# STM32L4xx-v1_1_0.net
KiCad netlist of a schematic drawn in EAGLE
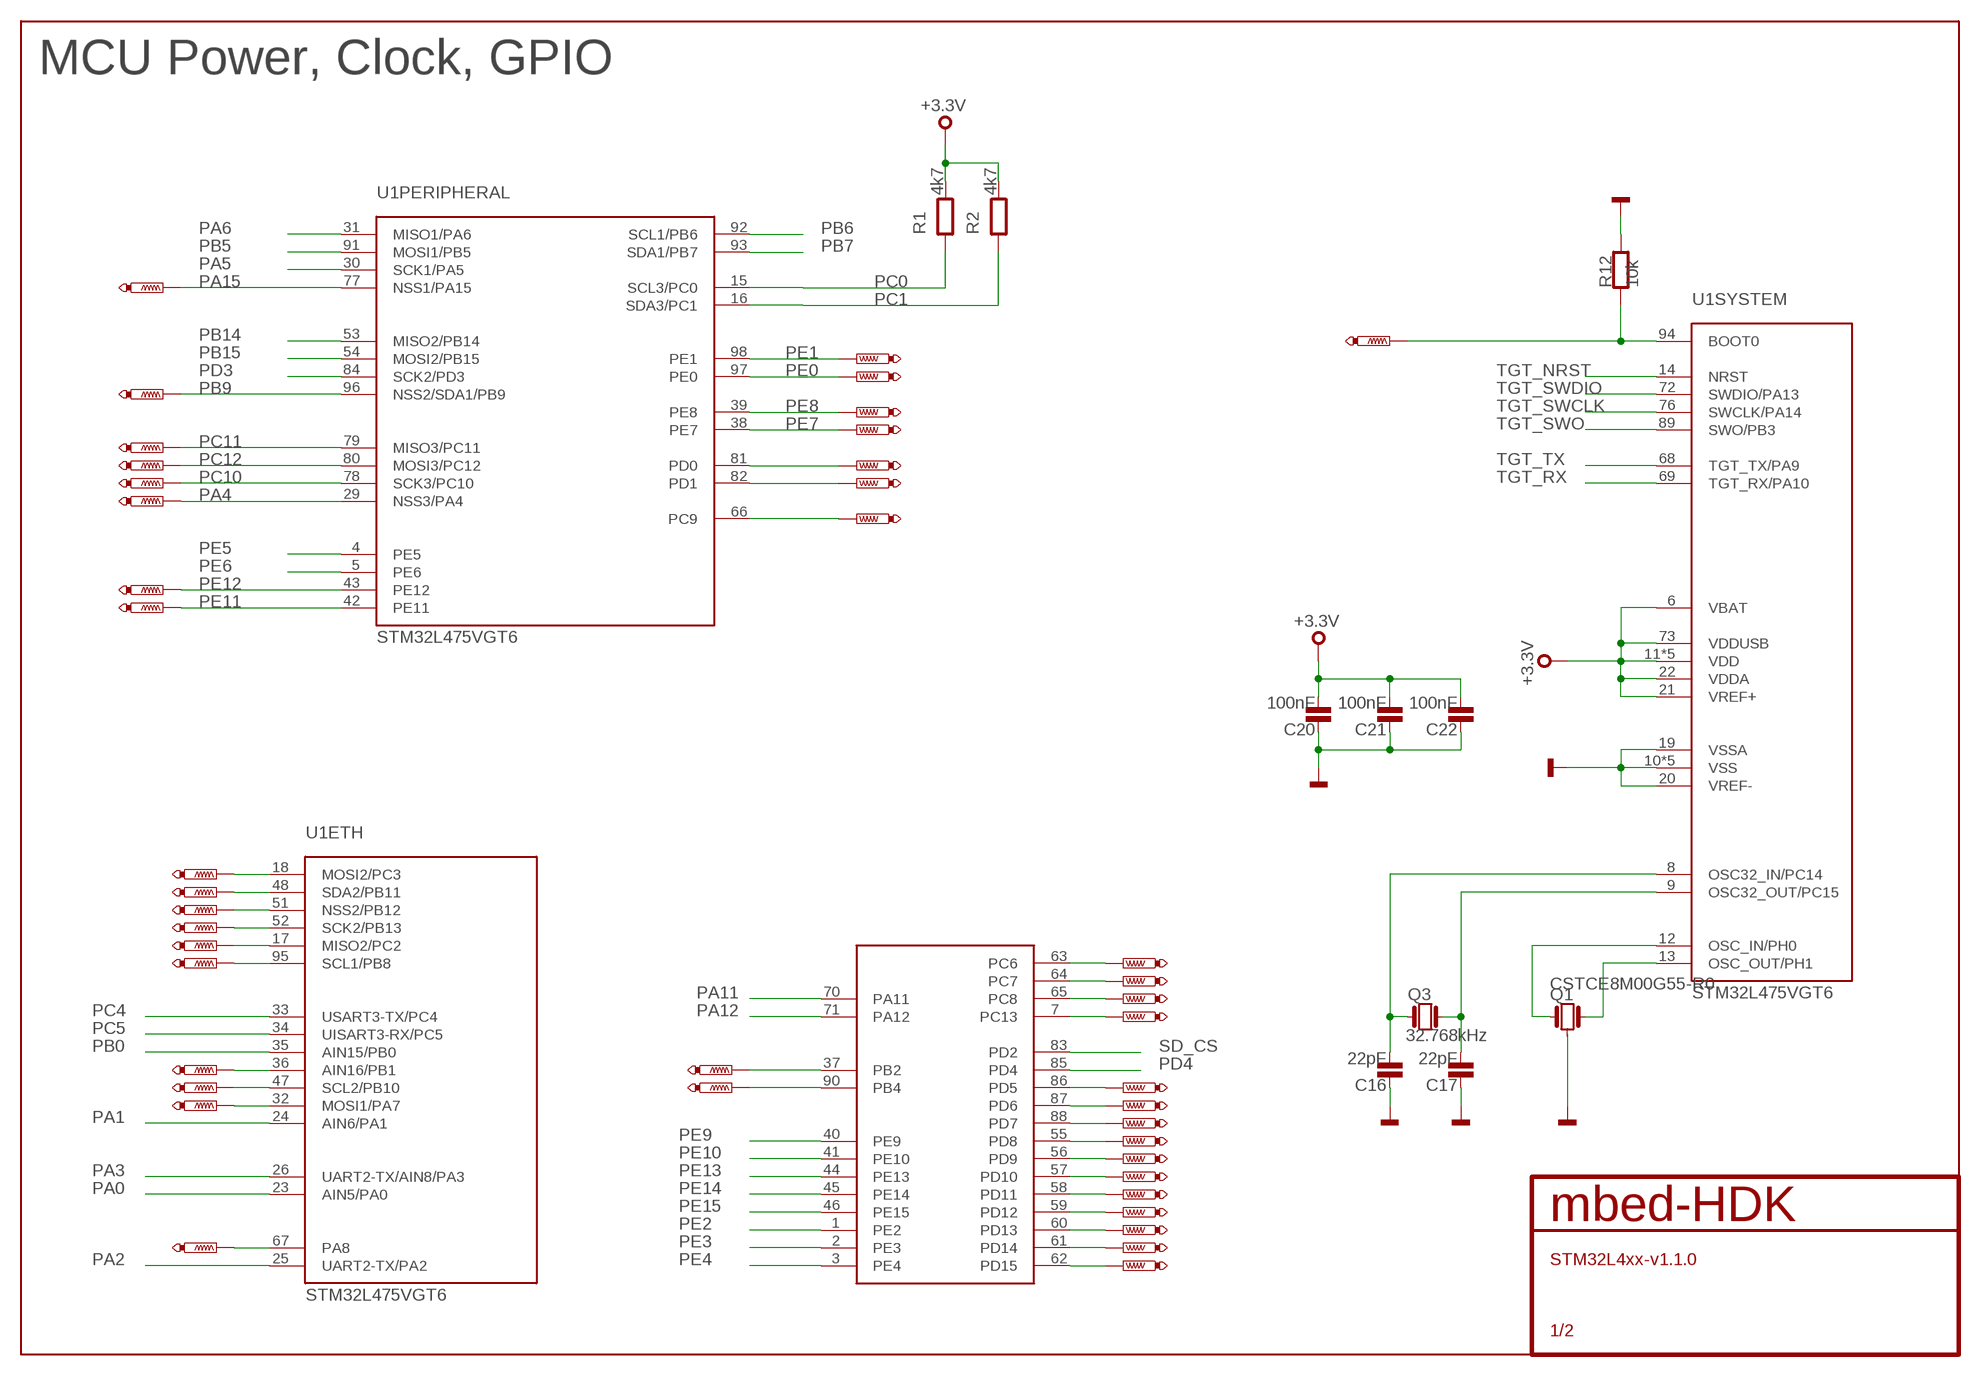
[diagram p0: schematic, sheet 1]
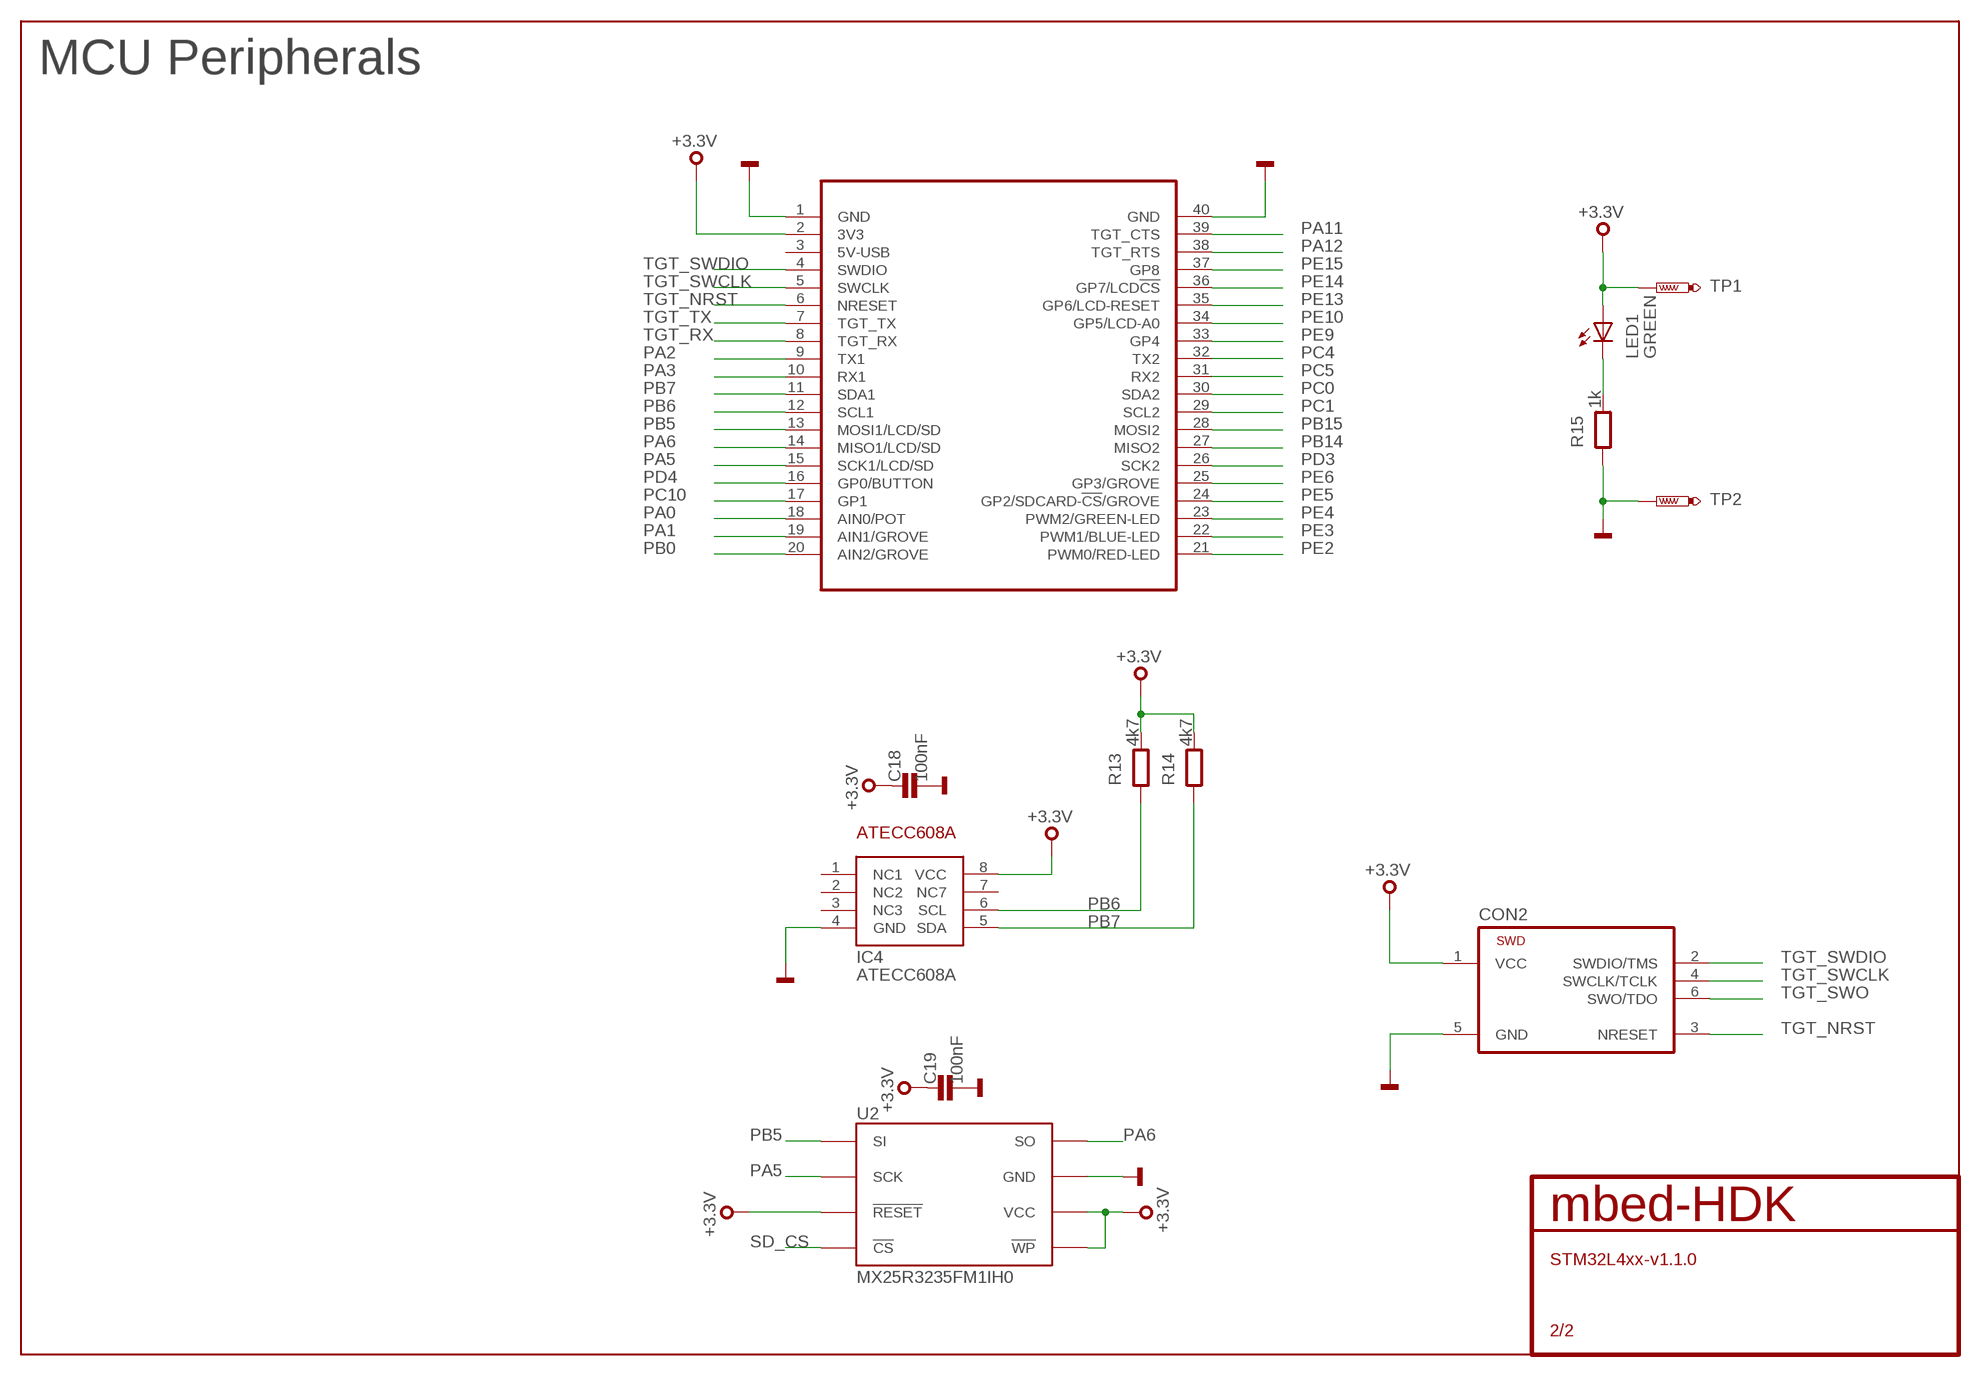
[diagram p1: schematic, sheet 2]

(export (version "E")
  (design (tool "Eeschema 10.0.6"))
  (components
    (comp (ref "C18")
      (value "100nF")
      (footprint "eagle-import:0402")
      (libsource (lib "eagle-import") (part "C0402"))
    )
    (comp (ref "C19")
      (value "100nF")
      (footprint "eagle-import:0402")
      (libsource (lib "eagle-import") (part "C0402"))
    )
    (comp (ref "CON2")
      (value "TC2030-CTX-NL")
      (footprint "eagle-import:TC2030-CTX-NL")
      (libsource (lib "eagle-import") (part "TC2030-CTX-NL"))
    )
    (comp (ref "IC4")
      (value "ATECC608A")
      (footprint "eagle-import:SO8")
      (libsource (lib "eagle-import") (part "ATECC608A"))
    )
    (comp (ref "LED1")
      (value "GREEN")
      (footprint "eagle-import:CHIPLED_0603")
      (fields (field (name "MF") "Wurth Electronics Inc"))
      (libsource (lib "eagle-import") (part "SMD_LED0603"))
    )
    (comp (ref "MOD1")
      (value "MODULE_DAUGHTER")
      (footprint "eagle-import:MODULE_DAUGHTER")
      (libsource (lib "eagle-import") (part "MODULE_DAUGHTER"))
    )
    (comp (ref "R13")
      (value "4k7")
      (footprint "eagle-import:0402")
      (libsource (lib "eagle-import") (part "R0402"))
    )
    (comp (ref "R14")
      (value "4k7")
      (footprint "eagle-import:0402")
      (libsource (lib "eagle-import") (part "R0402"))
    )
    (comp (ref "R15")
      (value "1k")
      (footprint "eagle-import:0603")
      (libsource (lib "eagle-import") (part "R0603"))
    )
    (comp (ref "TP1")
      (value "TEST-POINT-50R-PTH")
      (footprint "eagle-import:TP50-PTH")
      (libsource (lib "eagle-import") (part "TEST-POINT-50R-PTH"))
    )
    (comp (ref "TP2")
      (value "TEST-POINT-50R-PTH")
      (footprint "eagle-import:TP50-PTH")
      (libsource (lib "eagle-import") (part "TEST-POINT-50R-PTH"))
    )
    (comp (ref "U2")
      (value "MX25R3235FM1IH0")
      (footprint "eagle-import:SO8")
      (fields (field (name "MF") "Macronix"))
      (libsource (lib "eagle-import") (part "MX25R3235FM1IH0"))
    )
    (comp (ref "C16")
      (value "22pF")
      (footprint "eagle-import:0603")
      (libsource (lib "eagle-import") (part "C0603"))
    )
    (comp (ref "C17")
      (value "22pF")
      (footprint "eagle-import:0603")
      (libsource (lib "eagle-import") (part "C0603"))
    )
    (comp (ref "C20")
      (value "100nF")
      (footprint "eagle-import:0402")
      (libsource (lib "eagle-import") (part "C0402"))
    )
    (comp (ref "C21")
      (value "100nF")
      (footprint "eagle-import:0402")
      (libsource (lib "eagle-import") (part "C0402"))
    )
    (comp (ref "C22")
      (value "100nF")
      (footprint "eagle-import:0402")
      (libsource (lib "eagle-import") (part "C0402"))
    )
    (comp (ref "Q1")
      (value "CSTCE8M00G55-R0")
      (footprint "eagle-import:CSTCE8M00G55-R0")
      (fields (field (name "MF") "Murata"))
      (libsource (lib "eagle-import") (part "CSTCE8M00G55-R0"))
    )
    (comp (ref "Q3")
      (value "32.768kHz")
      (footprint "eagle-import:FC135")
      (libsource (lib "eagle-import") (part "GENERIC-CRYSTAL_FC135"))
    )
    (comp (ref "R1")
      (value "4k7")
      (footprint "eagle-import:0402")
      (libsource (lib "eagle-import") (part "R0402"))
    )
    (comp (ref "R2")
      (value "4k7")
      (footprint "eagle-import:0402")
      (libsource (lib "eagle-import") (part "R0402"))
    )
    (comp (ref "R12")
      (value "10k")
      (footprint "eagle-import:0402")
      (libsource (lib "eagle-import") (part "R0402"))
    )
    (comp (ref "TP3")
      (value "PTR1TP06R")
      (footprint "eagle-import:TP06R")
      (libsource (lib "eagle-import") (part "PTR1TP06R"))
    )
    (comp (ref "TP4")
      (value "PTR1TP06R")
      (footprint "eagle-import:TP06R")
      (libsource (lib "eagle-import") (part "PTR1TP06R"))
    )
    (comp (ref "TP5")
      (value "PTR1TP06R")
      (footprint "eagle-import:TP06R")
      (libsource (lib "eagle-import") (part "PTR1TP06R"))
    )
    (comp (ref "TP6")
      (value "PTR1TP06R")
      (footprint "eagle-import:TP06R")
      (libsource (lib "eagle-import") (part "PTR1TP06R"))
    )
    (comp (ref "TP7")
      (value "PTR1TP06R")
      (footprint "eagle-import:TP06R")
      (libsource (lib "eagle-import") (part "PTR1TP06R"))
    )
    (comp (ref "TP8")
      (value "PTR1TP06R")
      (footprint "eagle-import:TP06R")
      (libsource (lib "eagle-import") (part "PTR1TP06R"))
    )
    (comp (ref "TP9")
      (value "PTR1TP06R")
      (footprint "eagle-import:TP06R")
      (libsource (lib "eagle-import") (part "PTR1TP06R"))
    )
    (comp (ref "TP10")
      (value "PTR1TP06R")
      (footprint "eagle-import:TP06R")
      (libsource (lib "eagle-import") (part "PTR1TP06R"))
    )
    (comp (ref "TP11")
      (value "PTR1TP06R")
      (footprint "eagle-import:TP06R")
      (libsource (lib "eagle-import") (part "PTR1TP06R"))
    )
    (comp (ref "TP12")
      (value "PTR1TP06R")
      (footprint "eagle-import:TP06R")
      (libsource (lib "eagle-import") (part "PTR1TP06R"))
    )
    (comp (ref "TP13")
      (value "PTR1TP06R")
      (footprint "eagle-import:TP06R")
      (libsource (lib "eagle-import") (part "PTR1TP06R"))
    )
    (comp (ref "TP14")
      (value "PTR1TP06R")
      (footprint "eagle-import:TP06R")
      (libsource (lib "eagle-import") (part "PTR1TP06R"))
    )
    (comp (ref "TP15")
      (value "PTR1TP06R")
      (footprint "eagle-import:TP06R")
      (libsource (lib "eagle-import") (part "PTR1TP06R"))
    )
    (comp (ref "TP16")
      (value "PTR1TP06R")
      (footprint "eagle-import:TP06R")
      (libsource (lib "eagle-import") (part "PTR1TP06R"))
    )
    (comp (ref "TP17")
      (value "PTR1TP06R")
      (footprint "eagle-import:TP06R")
      (libsource (lib "eagle-import") (part "PTR1TP06R"))
    )
    (comp (ref "TP18")
      (value "PTR1TP06R")
      (footprint "eagle-import:TP06R")
      (libsource (lib "eagle-import") (part "PTR1TP06R"))
    )
    (comp (ref "TP19")
      (value "PTR1TP06R")
      (footprint "eagle-import:TP06R")
      (libsource (lib "eagle-import") (part "PTR1TP06R"))
    )
    (comp (ref "TP20")
      (value "PTR1TP06R")
      (footprint "eagle-import:TP06R")
      (libsource (lib "eagle-import") (part "PTR1TP06R"))
    )
    (comp (ref "TP21")
      (value "PTR1TP06R")
      (footprint "eagle-import:TP06R")
      (libsource (lib "eagle-import") (part "PTR1TP06R"))
    )
    (comp (ref "TP22")
      (value "PTR1TP06R")
      (footprint "eagle-import:TP06R")
      (libsource (lib "eagle-import") (part "PTR1TP06R"))
    )
    (comp (ref "TP23")
      (value "PTR1TP06R")
      (footprint "eagle-import:TP06R")
      (libsource (lib "eagle-import") (part "PTR1TP06R"))
    )
    (comp (ref "TP24")
      (value "PTR1TP06R")
      (footprint "eagle-import:TP06R")
      (libsource (lib "eagle-import") (part "PTR1TP06R"))
    )
    (comp (ref "TP25")
      (value "PTR1TP06R")
      (footprint "eagle-import:TP06R")
      (libsource (lib "eagle-import") (part "PTR1TP06R"))
    )
    (comp (ref "TP26")
      (value "PTR1TP06R")
      (footprint "eagle-import:TP06R")
      (libsource (lib "eagle-import") (part "PTR1TP06R"))
    )
    (comp (ref "TP27")
      (value "PTR1TP06R")
      (footprint "eagle-import:TP06R")
      (libsource (lib "eagle-import") (part "PTR1TP06R"))
    )
    (comp (ref "TP28")
      (value "PTR1TP06R")
      (footprint "eagle-import:TP06R")
      (libsource (lib "eagle-import") (part "PTR1TP06R"))
    )
    (comp (ref "TP29")
      (value "PTR1TP06R")
      (footprint "eagle-import:TP06R")
      (libsource (lib "eagle-import") (part "PTR1TP06R"))
    )
    (comp (ref "TP30")
      (value "PTR1TP06R")
      (footprint "eagle-import:TP06R")
      (libsource (lib "eagle-import") (part "PTR1TP06R"))
    )
    (comp (ref "TP31")
      (value "PTR1TP06R")
      (footprint "eagle-import:TP06R")
      (libsource (lib "eagle-import") (part "PTR1TP06R"))
    )
    (comp (ref "TP32")
      (value "PTR1TP06R")
      (footprint "eagle-import:TP06R")
      (libsource (lib "eagle-import") (part "PTR1TP06R"))
    )
    (comp (ref "TP33")
      (value "PTR1TP06R")
      (footprint "eagle-import:TP06R")
      (libsource (lib "eagle-import") (part "PTR1TP06R"))
    )
    (comp (ref "TP34")
      (value "PTR1TP06R")
      (footprint "eagle-import:TP06R")
      (libsource (lib "eagle-import") (part "PTR1TP06R"))
    )
    (comp (ref "TP35")
      (value "PTR1TP06R")
      (footprint "eagle-import:TP06R")
      (libsource (lib "eagle-import") (part "PTR1TP06R"))
    )
    (comp (ref "TP36")
      (value "PTR1TP06R")
      (footprint "eagle-import:TP06R")
      (libsource (lib "eagle-import") (part "PTR1TP06R"))
    )
    (comp (ref "TP37")
      (value "PTR1TP06R")
      (footprint "eagle-import:TP06R")
      (libsource (lib "eagle-import") (part "PTR1TP06R"))
    )
    (comp (ref "TP38")
      (value "PTR1TP06R")
      (footprint "eagle-import:TP06R")
      (libsource (lib "eagle-import") (part "PTR1TP06R"))
    )
    (comp (ref "TP39")
      (value "PTR1TP06R")
      (footprint "eagle-import:TP06R")
      (libsource (lib "eagle-import") (part "PTR1TP06R"))
    )
    (comp (ref "TP40")
      (value "PTR1TP06R")
      (footprint "eagle-import:TP06R")
      (libsource (lib "eagle-import") (part "PTR1TP06R"))
    )
    (comp (ref "TP41")
      (value "PTR1TP06R")
      (footprint "eagle-import:TP06R")
      (libsource (lib "eagle-import") (part "PTR1TP06R"))
    )
    (comp (ref "TP42")
      (value "PTR1TP06R")
      (footprint "eagle-import:TP06R")
      (libsource (lib "eagle-import") (part "PTR1TP06R"))
    )
    (comp (ref "TP43")
      (value "PTR1TP06R")
      (footprint "eagle-import:TP06R")
      (libsource (lib "eagle-import") (part "PTR1TP06R"))
    )
    (comp (ref "TP44")
      (value "PTR1TP06R")
      (footprint "eagle-import:TP06R")
      (libsource (lib "eagle-import") (part "PTR1TP06R"))
    )
    (comp (ref "TP45")
      (value "PTR1TP06R")
      (footprint "eagle-import:TP06R")
      (libsource (lib "eagle-import") (part "PTR1TP06R"))
    )
    (comp (ref "U1")
      (value "STM32L475VGT6")
      (footprint "eagle-import:QFP50P1600X1600X160-100N")
      (libsource (lib "eagle-import") (part "STM32L475VGT6"))
    )
  )
  (nets
    (net (code "1") (name "+3.3V") (class "Default")
      (node (ref "C18") (pin "1") (pinfunction "P$1_1") (pintype "passive"))
      (node (ref "C19") (pin "1") (pinfunction "P$1_1") (pintype "passive"))
      (node (ref "C20") (pin "2") (pinfunction "P$2_2") (pintype "passive"))
      (node (ref "C21") (pin "2") (pinfunction "P$2_2") (pintype "passive"))
      (node (ref "C22") (pin "2") (pinfunction "P$2_2") (pintype "passive"))
      (node (ref "CON2") (pin "1") (pinfunction "VCC_1") (pintype "passive"))
      (node (ref "IC4") (pin "8") (pinfunction "VCC_8") (pintype "bidirectional"))
      (node (ref "LED1") (pin "A") (pinfunction "A_A") (pintype "passive"))
      (node (ref "MOD1") (pin "2") (pinfunction "3V3_2") (pintype "bidirectional"))
      (node (ref "R1") (pin "2") (pinfunction "P$2_2") (pintype "passive"))
      (node (ref "R13") (pin "2") (pinfunction "P$2_2") (pintype "passive"))
      (node (ref "R14") (pin "2") (pinfunction "P$2_2") (pintype "passive"))
      (node (ref "R2") (pin "2") (pinfunction "P$2_2") (pintype "passive"))
      (node (ref "TP1") (pin "TP") (pinfunction "TP_TP") (pintype "input"))
      (node (ref "U1") (pin "100") (pinfunction "VDD_100") (pintype "power_in"))
      (node (ref "U1") (pin "11") (pinfunction "VDD_11") (pintype "power_in"))
      (node (ref "U1") (pin "21") (pinfunction "VREF+_21") (pintype "power_in"))
      (node (ref "U1") (pin "22") (pinfunction "VDDA_22") (pintype "power_in"))
      (node (ref "U1") (pin "28") (pinfunction "VDD_28") (pintype "power_in"))
      (node (ref "U1") (pin "50") (pinfunction "VDD_50") (pintype "power_in"))
      (node (ref "U1") (pin "6") (pinfunction "VBAT_6") (pintype "power_in"))
      (node (ref "U1") (pin "73") (pinfunction "VDDUSB_73") (pintype "power_in"))
      (node (ref "U1") (pin "75") (pinfunction "VDD_75") (pintype "power_in"))
      (node (ref "U2") (pin "3") (pinfunction "~{WP}_3") (pintype "bidirectional"))
      (node (ref "U2") (pin "7") (pinfunction "~{RESET}_7") (pintype "bidirectional"))
      (node (ref "U2") (pin "8") (pinfunction "VCC_8") (pintype "bidirectional"))
    )
    (net (code "2") (name "GND") (class "Default")
      (node (ref "C16") (pin "1") (pinfunction "P$1_1") (pintype "passive"))
      (node (ref "C17") (pin "1") (pinfunction "P$1_1") (pintype "passive"))
      (node (ref "C18") (pin "2") (pinfunction "P$2_2") (pintype "passive"))
      (node (ref "C19") (pin "2") (pinfunction "P$2_2") (pintype "passive"))
      (node (ref "C20") (pin "1") (pinfunction "P$1_1") (pintype "passive"))
      (node (ref "C21") (pin "1") (pinfunction "P$1_1") (pintype "passive"))
      (node (ref "C22") (pin "1") (pinfunction "P$1_1") (pintype "passive"))
      (node (ref "CON2") (pin "5") (pinfunction "GND_5") (pintype "passive"))
      (node (ref "IC4") (pin "4") (pinfunction "GND_4") (pintype "bidirectional"))
      (node (ref "MOD1") (pin "1") (pinfunction "GND_1") (pintype "bidirectional"))
      (node (ref "MOD1") (pin "40") (pinfunction "GND_40") (pintype "bidirectional"))
      (node (ref "Q1") (pin "2") (pinfunction "2_2") (pintype "passive"))
      (node (ref "R12") (pin "2") (pinfunction "P$2_2") (pintype "passive"))
      (node (ref "R15") (pin "1") (pinfunction "P$1_1") (pintype "passive"))
      (node (ref "TP2") (pin "TP") (pinfunction "TP_TP") (pintype "input"))
      (node (ref "U1") (pin "10") (pinfunction "VSS_10") (pintype "power_in"))
      (node (ref "U1") (pin "19") (pinfunction "VSSA_19") (pintype "power_in"))
      (node (ref "U1") (pin "20") (pinfunction "VREF-_20") (pintype "power_in"))
      (node (ref "U1") (pin "27") (pinfunction "VSS_27") (pintype "power_in"))
      (node (ref "U1") (pin "49") (pinfunction "VSS_49") (pintype "power_in"))
      (node (ref "U1") (pin "74") (pinfunction "VSS_74") (pintype "power_in"))
      (node (ref "U1") (pin "99") (pinfunction "VSS_99") (pintype "power_in"))
      (node (ref "U2") (pin "4") (pinfunction "GND_4") (pintype "bidirectional"))
    )
    (net (code "3") (name "Net-(C16-P$2)") (class "Default")
      (node (ref "C16") (pin "2") (pinfunction "P$2_2") (pintype "passive"))
      (node (ref "Q3") (pin "X1") (pinfunction "1_X1") (pintype "passive"))
      (node (ref "U1") (pin "8") (pinfunction "OSC32_IN/PC14_8") (pintype "bidirectional"))
    )
    (net (code "4") (name "Net-(C17-P$2)") (class "Default")
      (node (ref "C17") (pin "2") (pinfunction "P$2_2") (pintype "passive"))
      (node (ref "Q3") (pin "X2") (pinfunction "2_X2") (pintype "passive"))
      (node (ref "U1") (pin "9") (pinfunction "OSC32_OUT/PC15_9") (pintype "bidirectional"))
    )
    (net (code "5") (name "Net-(R12-P$1)") (class "Default")
      (node (ref "R12") (pin "1") (pinfunction "P$1_1") (pintype "passive"))
      (node (ref "TP6") (pin "TP") (pinfunction "TP_TP") (pintype "input"))
      (node (ref "U1") (pin "94") (pinfunction "BOOT0_94") (pintype "input"))
    )
    (net (code "6") (name "Net-(R15-P$2)") (class "Default")
      (node (ref "LED1") (pin "C") (pinfunction "C_C") (pintype "passive"))
      (node (ref "R15") (pin "2") (pinfunction "P$2_2") (pintype "passive"))
    )
    (net (code "7") (name "Net-(U1A-AIN16{slash}PB1)") (class "Default")
      (node (ref "TP34") (pin "TP") (pinfunction "TP_TP") (pintype "input"))
      (node (ref "U1") (pin "36") (pinfunction "AIN16/PB1_36") (pintype "bidirectional"))
    )
    (net (code "8") (name "Net-(U1A-MISO2{slash}PC2)") (class "Default")
      (node (ref "TP31") (pin "TP") (pinfunction "TP_TP") (pintype "input"))
      (node (ref "U1") (pin "17") (pinfunction "MISO2/PC2_17") (pintype "bidirectional"))
    )
    (net (code "9") (name "Net-(U1A-MOSI1{slash}PA7)") (class "Default")
      (node (ref "TP35") (pin "TP") (pinfunction "TP_TP") (pintype "input"))
      (node (ref "U1") (pin "32") (pinfunction "MOSI1/PA7_32") (pintype "bidirectional"))
    )
    (net (code "10") (name "Net-(U1A-MOSI2{slash}PC3)") (class "Default")
      (node (ref "TP27") (pin "TP") (pinfunction "TP_TP") (pintype "input"))
      (node (ref "U1") (pin "18") (pinfunction "MOSI2/PC3_18") (pintype "bidirectional"))
    )
    (net (code "11") (name "Net-(U1A-NSS2{slash}PB12)") (class "Default")
      (node (ref "TP29") (pin "TP") (pinfunction "TP_TP") (pintype "input"))
      (node (ref "U1") (pin "51") (pinfunction "NSS2/PB12_51") (pintype "bidirectional"))
    )
    (net (code "12") (name "Net-(U1A-PA8)") (class "Default")
      (node (ref "TP33") (pin "TP") (pinfunction "TP_TP") (pintype "input"))
      (node (ref "U1") (pin "67") (pinfunction "PA8_67") (pintype "bidirectional"))
    )
    (net (code "13") (name "Net-(U1A-SCK2{slash}PB13)") (class "Default")
      (node (ref "TP30") (pin "TP") (pinfunction "TP_TP") (pintype "input"))
      (node (ref "U1") (pin "52") (pinfunction "SCK2/PB13_52") (pintype "bidirectional"))
    )
    (net (code "14") (name "Net-(U1A-SCL1{slash}PB8)") (class "Default")
      (node (ref "TP32") (pin "TP") (pinfunction "TP_TP") (pintype "input"))
      (node (ref "U1") (pin "95") (pinfunction "SCL1/PB8_95") (pintype "bidirectional"))
    )
    (net (code "15") (name "Net-(U1A-SCL2{slash}PB10)") (class "Default")
      (node (ref "TP36") (pin "TP") (pinfunction "TP_TP") (pintype "input"))
      (node (ref "U1") (pin "47") (pinfunction "SCL2/PB10_47") (pintype "bidirectional"))
    )
    (net (code "16") (name "Net-(U1A-SDA2{slash}PB11)") (class "Default")
      (node (ref "TP28") (pin "TP") (pinfunction "TP_TP") (pintype "input"))
      (node (ref "U1") (pin "48") (pinfunction "SDA2/PB11_48") (pintype "bidirectional"))
    )
    (net (code "17") (name "Net-(U1B-PB2)") (class "Default")
      (node (ref "TP26") (pin "TP") (pinfunction "TP_TP") (pintype "input"))
      (node (ref "U1") (pin "37") (pinfunction "PB2_37") (pintype "bidirectional"))
    )
    (net (code "18") (name "Net-(U1B-PB4)") (class "Default")
      (node (ref "TP11") (pin "TP") (pinfunction "TP_TP") (pintype "input"))
      (node (ref "U1") (pin "90") (pinfunction "PB4_90") (pintype "bidirectional"))
    )
    (net (code "19") (name "Net-(U1B-PC6)") (class "Default")
      (node (ref "TP15") (pin "TP") (pinfunction "TP_TP") (pintype "input"))
      (node (ref "U1") (pin "63") (pinfunction "PC6_63") (pintype "bidirectional"))
    )
    (net (code "20") (name "Net-(U1B-PC7)") (class "Default")
      (node (ref "TP16") (pin "TP") (pinfunction "TP_TP") (pintype "input"))
      (node (ref "U1") (pin "64") (pinfunction "PC7_64") (pintype "bidirectional"))
    )
    (net (code "21") (name "Net-(U1B-PC8)") (class "Default")
      (node (ref "TP17") (pin "TP") (pinfunction "TP_TP") (pintype "input"))
      (node (ref "U1") (pin "65") (pinfunction "PC8_65") (pintype "bidirectional"))
    )
    (net (code "22") (name "Net-(U1B-PC13)") (class "Default")
      (node (ref "TP25") (pin "TP") (pinfunction "TP_TP") (pintype "input"))
      (node (ref "U1") (pin "7") (pinfunction "PC13_7") (pintype "bidirectional"))
    )
    (net (code "23") (name "Net-(U1B-PD5)") (class "Default")
      (node (ref "TP20") (pin "TP") (pinfunction "TP_TP") (pintype "input"))
      (node (ref "U1") (pin "86") (pinfunction "PD5_86") (pintype "bidirectional"))
    )
    (net (code "24") (name "Net-(U1B-PD6)") (class "Default")
      (node (ref "TP19") (pin "TP") (pinfunction "TP_TP") (pintype "input"))
      (node (ref "U1") (pin "87") (pinfunction "PD6_87") (pintype "bidirectional"))
    )
    (net (code "25") (name "Net-(U1B-PD7)") (class "Default")
      (node (ref "TP18") (pin "TP") (pinfunction "TP_TP") (pintype "input"))
      (node (ref "U1") (pin "88") (pinfunction "PD7_88") (pintype "bidirectional"))
    )
    (net (code "26") (name "Net-(U1B-PD8)") (class "Default")
      (node (ref "TP5") (pin "TP") (pinfunction "TP_TP") (pintype "input"))
      (node (ref "U1") (pin "55") (pinfunction "PD8_55") (pintype "bidirectional"))
    )
    (net (code "27") (name "Net-(U1B-PD9)") (class "Default")
      (node (ref "TP13") (pin "TP") (pinfunction "TP_TP") (pintype "input"))
      (node (ref "U1") (pin "56") (pinfunction "PD9_56") (pintype "bidirectional"))
    )
    (net (code "28") (name "Net-(U1B-PD10)") (class "Default")
      (node (ref "TP10") (pin "TP") (pinfunction "TP_TP") (pintype "input"))
      (node (ref "U1") (pin "57") (pinfunction "PD10_57") (pintype "bidirectional"))
    )
    (net (code "29") (name "Net-(U1B-PD11)") (class "Default")
      (node (ref "TP22") (pin "TP") (pinfunction "TP_TP") (pintype "input"))
      (node (ref "U1") (pin "58") (pinfunction "PD11_58") (pintype "bidirectional"))
    )
    (net (code "30") (name "Net-(U1B-PD12)") (class "Default")
      (node (ref "TP23") (pin "TP") (pinfunction "TP_TP") (pintype "input"))
      (node (ref "U1") (pin "59") (pinfunction "PD12_59") (pintype "bidirectional"))
    )
    (net (code "31") (name "Net-(U1B-PD13)") (class "Default")
      (node (ref "TP12") (pin "TP") (pinfunction "TP_TP") (pintype "input"))
      (node (ref "U1") (pin "60") (pinfunction "PD13_60") (pintype "bidirectional"))
    )
    (net (code "32") (name "Net-(U1B-PD14)") (class "Default")
      (node (ref "TP24") (pin "TP") (pinfunction "TP_TP") (pintype "input"))
      (node (ref "U1") (pin "61") (pinfunction "PD14_61") (pintype "bidirectional"))
    )
    (net (code "33") (name "Net-(U1B-PD15)") (class "Default")
      (node (ref "TP21") (pin "TP") (pinfunction "TP_TP") (pintype "input"))
      (node (ref "U1") (pin "62") (pinfunction "PD15_62") (pintype "bidirectional"))
    )
    (net (code "34") (name "Net-(U1C-PC9)") (class "Default")
      (node (ref "TP7") (pin "TP") (pinfunction "TP_TP") (pintype "input"))
      (node (ref "U1") (pin "66") (pinfunction "PC9_66") (pintype "bidirectional"))
    )
    (net (code "35") (name "Net-(U1C-PD0)") (class "Default")
      (node (ref "TP3") (pin "TP") (pinfunction "TP_TP") (pintype "input"))
      (node (ref "U1") (pin "81") (pinfunction "PD0_81") (pintype "bidirectional"))
    )
    (net (code "36") (name "Net-(U1C-PD1)") (class "Default")
      (node (ref "TP4") (pin "TP") (pinfunction "TP_TP") (pintype "input"))
      (node (ref "U1") (pin "82") (pinfunction "PD1_82") (pintype "bidirectional"))
    )
    (net (code "37") (name "Net-(U1D-OSC_IN{slash}PH0)") (class "Default")
      (node (ref "Q1") (pin "1") (pinfunction "1_1") (pintype "passive"))
      (node (ref "U1") (pin "12") (pinfunction "OSC_IN/PH0_12") (pintype "bidirectional"))
    )
    (net (code "38") (name "Net-(U1D-OSC_OUT{slash}PH1)") (class "Default")
      (node (ref "Q1") (pin "3") (pinfunction "3_3") (pintype "passive"))
      (node (ref "U1") (pin "13") (pinfunction "OSC_OUT/PH1_13") (pintype "bidirectional"))
    )
    (net (code "39") (name "PA0") (class "Default")
      (node (ref "MOD1") (pin "18") (pinfunction "AIN0/POT_18") (pintype "bidirectional"))
      (node (ref "U1") (pin "23") (pinfunction "AIN5/PA0_23") (pintype "bidirectional"))
    )
    (net (code "40") (name "PA1") (class "Default")
      (node (ref "MOD1") (pin "19") (pinfunction "AIN1/GROVE_19") (pintype "bidirectional"))
      (node (ref "U1") (pin "24") (pinfunction "AIN6/PA1_24") (pintype "bidirectional"))
    )
    (net (code "41") (name "PA2") (class "Default")
      (node (ref "MOD1") (pin "9") (pinfunction "TX1_9") (pintype "bidirectional"))
      (node (ref "U1") (pin "25") (pinfunction "UART2-TX/PA2_25") (pintype "bidirectional"))
    )
    (net (code "42") (name "PA3") (class "Default")
      (node (ref "MOD1") (pin "10") (pinfunction "RX1_10") (pintype "bidirectional"))
      (node (ref "U1") (pin "26") (pinfunction "UART2-TX/AIN8/PA3_26") (pintype "bidirectional"))
    )
    (net (code "43") (name "PA4") (class "Default")
      (node (ref "TP44") (pin "TP") (pinfunction "TP_TP") (pintype "input"))
      (node (ref "U1") (pin "29") (pinfunction "NSS3/PA4_29") (pintype "bidirectional"))
    )
    (net (code "44") (name "PA5") (class "Default")
      (node (ref "MOD1") (pin "15") (pinfunction "SCK1/LCD/SD_15") (pintype "bidirectional"))
      (node (ref "U1") (pin "30") (pinfunction "SCK1/PA5_30") (pintype "bidirectional"))
      (node (ref "U2") (pin "6") (pinfunction "SCK_6") (pintype "bidirectional"))
    )
    (net (code "45") (name "PA6") (class "Default")
      (node (ref "MOD1") (pin "14") (pinfunction "MISO1/LCD/SD_14") (pintype "bidirectional"))
      (node (ref "U1") (pin "31") (pinfunction "MISO1/PA6_31") (pintype "bidirectional"))
      (node (ref "U2") (pin "2") (pinfunction "SO_2") (pintype "bidirectional"))
    )
    (net (code "46") (name "PA11") (class "Default")
      (node (ref "MOD1") (pin "39") (pinfunction "TGT_CTS_39") (pintype "bidirectional"))
      (node (ref "U1") (pin "70") (pinfunction "PA11_70") (pintype "bidirectional"))
    )
    (net (code "47") (name "PA12") (class "Default")
      (node (ref "MOD1") (pin "38") (pinfunction "TGT_RTS_38") (pintype "bidirectional"))
      (node (ref "U1") (pin "71") (pinfunction "PA12_71") (pintype "bidirectional"))
    )
    (net (code "48") (name "PA15") (class "Default")
      (node (ref "TP37") (pin "TP") (pinfunction "TP_TP") (pintype "input"))
      (node (ref "U1") (pin "77") (pinfunction "NSS1/PA15_77") (pintype "bidirectional"))
    )
    (net (code "49") (name "PB0") (class "Default")
      (node (ref "MOD1") (pin "20") (pinfunction "AIN2/GROVE_20") (pintype "bidirectional"))
      (node (ref "U1") (pin "35") (pinfunction "AIN15/PB0_35") (pintype "bidirectional"))
    )
    (net (code "50") (name "PB5") (class "Default")
      (node (ref "MOD1") (pin "13") (pinfunction "MOSI1/LCD/SD_13") (pintype "bidirectional"))
      (node (ref "U1") (pin "91") (pinfunction "MOSI1/PB5_91") (pintype "bidirectional"))
      (node (ref "U2") (pin "5") (pinfunction "SI_5") (pintype "bidirectional"))
    )
    (net (code "51") (name "PB6") (class "Default")
      (node (ref "IC4") (pin "6") (pinfunction "SCL_6") (pintype "bidirectional"))
      (node (ref "MOD1") (pin "12") (pinfunction "SCL1_12") (pintype "bidirectional"))
      (node (ref "R13") (pin "1") (pinfunction "P$1_1") (pintype "passive"))
      (node (ref "U1") (pin "92") (pinfunction "SCL1/PB6_92") (pintype "bidirectional"))
    )
    (net (code "52") (name "PB7") (class "Default")
      (node (ref "IC4") (pin "5") (pinfunction "SDA_5") (pintype "bidirectional"))
      (node (ref "MOD1") (pin "11") (pinfunction "SDA1_11") (pintype "bidirectional"))
      (node (ref "R14") (pin "1") (pinfunction "P$1_1") (pintype "passive"))
      (node (ref "U1") (pin "93") (pinfunction "SDA1/PB7_93") (pintype "bidirectional"))
    )
    (net (code "53") (name "PB9") (class "Default")
      (node (ref "TP14") (pin "TP") (pinfunction "TP_TP") (pintype "input"))
      (node (ref "U1") (pin "96") (pinfunction "NSS2/SDA1/PB9_96") (pintype "bidirectional"))
    )
    (net (code "54") (name "PB14") (class "Default")
      (node (ref "MOD1") (pin "27") (pinfunction "MISO2_27") (pintype "bidirectional"))
      (node (ref "U1") (pin "53") (pinfunction "MISO2/PB14_53") (pintype "bidirectional"))
    )
    (net (code "55") (name "PB15") (class "Default")
      (node (ref "MOD1") (pin "28") (pinfunction "MOSI2_28") (pintype "bidirectional"))
      (node (ref "U1") (pin "54") (pinfunction "MOSI2/PB15_54") (pintype "bidirectional"))
    )
    (net (code "56") (name "PC0") (class "Default")
      (node (ref "MOD1") (pin "30") (pinfunction "SDA2_30") (pintype "bidirectional"))
      (node (ref "R1") (pin "1") (pinfunction "P$1_1") (pintype "passive"))
      (node (ref "U1") (pin "15") (pinfunction "SCL3/PC0_15") (pintype "bidirectional"))
    )
    (net (code "57") (name "PC1") (class "Default")
      (node (ref "MOD1") (pin "29") (pinfunction "SCL2_29") (pintype "bidirectional"))
      (node (ref "R2") (pin "1") (pinfunction "P$1_1") (pintype "passive"))
      (node (ref "U1") (pin "16") (pinfunction "SDA3/PC1_16") (pintype "bidirectional"))
    )
    (net (code "58") (name "PC4") (class "Default")
      (node (ref "MOD1") (pin "32") (pinfunction "TX2_32") (pintype "bidirectional"))
      (node (ref "U1") (pin "33") (pinfunction "USART3-TX/PC4_33") (pintype "bidirectional"))
    )
    (net (code "59") (name "PC5") (class "Default")
      (node (ref "MOD1") (pin "31") (pinfunction "RX2_31") (pintype "bidirectional"))
      (node (ref "U1") (pin "34") (pinfunction "UISART3-RX/PC5_34") (pintype "bidirectional"))
    )
    (net (code "60") (name "PC10") (class "Default")
      (node (ref "MOD1") (pin "17") (pinfunction "GP1_17") (pintype "bidirectional"))
      (node (ref "TP43") (pin "TP") (pinfunction "TP_TP") (pintype "input"))
      (node (ref "U1") (pin "78") (pinfunction "SCK3/PC10_78") (pintype "bidirectional"))
    )
    (net (code "61") (name "PC11") (class "Default")
      (node (ref "TP41") (pin "TP") (pinfunction "TP_TP") (pintype "input"))
      (node (ref "U1") (pin "79") (pinfunction "MISO3/PC11_79") (pintype "bidirectional"))
    )
    (net (code "62") (name "PC12") (class "Default")
      (node (ref "TP42") (pin "TP") (pinfunction "TP_TP") (pintype "input"))
      (node (ref "U1") (pin "80") (pinfunction "MOSI3/PC12_80") (pintype "bidirectional"))
    )
    (net (code "63") (name "PD3") (class "Default")
      (node (ref "MOD1") (pin "26") (pinfunction "SCK2_26") (pintype "bidirectional"))
      (node (ref "U1") (pin "84") (pinfunction "SCK2/PD3_84") (pintype "bidirectional"))
    )
    (net (code "64") (name "PD4") (class "Default")
      (node (ref "MOD1") (pin "16") (pinfunction "GP0/BUTTON_16") (pintype "bidirectional"))
      (node (ref "U1") (pin "85") (pinfunction "PD4_85") (pintype "bidirectional"))
    )
    (net (code "65") (name "PE0") (class "Default")
      (node (ref "TP39") (pin "TP") (pinfunction "TP_TP") (pintype "input"))
      (node (ref "U1") (pin "97") (pinfunction "PE0_97") (pintype "bidirectional"))
    )
    (net (code "66") (name "PE1") (class "Default")
      (node (ref "TP38") (pin "TP") (pinfunction "TP_TP") (pintype "input"))
      (node (ref "U1") (pin "98") (pinfunction "PE1_98") (pintype "bidirectional"))
    )
    (net (code "67") (name "PE2") (class "Default")
      (node (ref "MOD1") (pin "21") (pinfunction "PWM0/RED-LED_21") (pintype "bidirectional"))
      (node (ref "U1") (pin "1") (pinfunction "PE2_1") (pintype "bidirectional"))
    )
    (net (code "68") (name "PE3") (class "Default")
      (node (ref "MOD1") (pin "22") (pinfunction "PWM1/BLUE-LED_22") (pintype "bidirectional"))
      (node (ref "U1") (pin "2") (pinfunction "PE3_2") (pintype "bidirectional"))
    )
    (net (code "69") (name "PE4") (class "Default")
      (node (ref "MOD1") (pin "23") (pinfunction "PWM2/GREEN-LED_23") (pintype "bidirectional"))
      (node (ref "U1") (pin "3") (pinfunction "PE4_3") (pintype "bidirectional"))
    )
    (net (code "70") (name "PE5") (class "Default")
      (node (ref "MOD1") (pin "24") (pinfunction "GP2/SDCARD-~{CS}/GROVE_24") (pintype "bidirectional"))
      (node (ref "U1") (pin "4") (pinfunction "PE5_4") (pintype "bidirectional"))
    )
    (net (code "71") (name "PE6") (class "Default")
      (node (ref "MOD1") (pin "25") (pinfunction "GP3/GROVE_25") (pintype "bidirectional"))
      (node (ref "U1") (pin "5") (pinfunction "PE6_5") (pintype "bidirectional"))
    )
    (net (code "72") (name "PE7") (class "Default")
      (node (ref "TP45") (pin "TP") (pinfunction "TP_TP") (pintype "input"))
      (node (ref "U1") (pin "38") (pinfunction "PE7_38") (pintype "bidirectional"))
    )
    (net (code "73") (name "PE8") (class "Default")
      (node (ref "TP40") (pin "TP") (pinfunction "TP_TP") (pintype "input"))
      (node (ref "U1") (pin "39") (pinfunction "PE8_39") (pintype "bidirectional"))
    )
    (net (code "74") (name "PE9") (class "Default")
      (node (ref "MOD1") (pin "33") (pinfunction "GP4_33") (pintype "bidirectional"))
      (node (ref "U1") (pin "40") (pinfunction "PE9_40") (pintype "bidirectional"))
    )
    (net (code "75") (name "PE10") (class "Default")
      (node (ref "MOD1") (pin "34") (pinfunction "GP5/LCD-A0_34") (pintype "bidirectional"))
      (node (ref "U1") (pin "41") (pinfunction "PE10_41") (pintype "bidirectional"))
    )
    (net (code "76") (name "PE11") (class "Default")
      (node (ref "TP8") (pin "TP") (pinfunction "TP_TP") (pintype "input"))
      (node (ref "U1") (pin "42") (pinfunction "PE11_42") (pintype "bidirectional"))
    )
    (net (code "77") (name "PE12") (class "Default")
      (node (ref "TP9") (pin "TP") (pinfunction "TP_TP") (pintype "input"))
      (node (ref "U1") (pin "43") (pinfunction "PE12_43") (pintype "bidirectional"))
    )
    (net (code "78") (name "PE13") (class "Default")
      (node (ref "MOD1") (pin "35") (pinfunction "GP6/LCD-RESET_35") (pintype "bidirectional"))
      (node (ref "U1") (pin "44") (pinfunction "PE13_44") (pintype "bidirectional"))
    )
    (net (code "79") (name "PE14") (class "Default")
      (node (ref "MOD1") (pin "36") (pinfunction "GP7/LCD~{CS}_36") (pintype "bidirectional"))
      (node (ref "U1") (pin "45") (pinfunction "PE14_45") (pintype "bidirectional"))
    )
    (net (code "80") (name "PE15") (class "Default")
      (node (ref "MOD1") (pin "37") (pinfunction "GP8_37") (pintype "bidirectional"))
      (node (ref "U1") (pin "46") (pinfunction "PE15_46") (pintype "bidirectional"))
    )
    (net (code "81") (name "SD_CS") (class "Default")
      (node (ref "U1") (pin "83") (pinfunction "PD2_83") (pintype "bidirectional"))
      (node (ref "U2") (pin "1") (pinfunction "~{CS}_1") (pintype "bidirectional"))
    )
    (net (code "82") (name "TGT_NRST") (class "Default")
      (node (ref "CON2") (pin "3") (pinfunction "NRESET_3") (pintype "passive"))
      (node (ref "MOD1") (pin "6") (pinfunction "NRESET_6") (pintype "bidirectional"))
      (node (ref "U1") (pin "14") (pinfunction "NRST_14") (pintype "bidirectional"))
    )
    (net (code "83") (name "TGT_RX") (class "Default")
      (node (ref "MOD1") (pin "8") (pinfunction "TGT_RX_8") (pintype "bidirectional"))
      (node (ref "U1") (pin "69") (pinfunction "TGT_RX/PA10_69") (pintype "bidirectional"))
    )
    (net (code "84") (name "TGT_SWCLK") (class "Default")
      (node (ref "CON2") (pin "4") (pinfunction "SWCLK/TCLK_4") (pintype "passive"))
      (node (ref "MOD1") (pin "5") (pinfunction "SWCLK_5") (pintype "bidirectional"))
      (node (ref "U1") (pin "76") (pinfunction "SWCLK/PA14_76") (pintype "bidirectional"))
    )
    (net (code "85") (name "TGT_SWDIO") (class "Default")
      (node (ref "CON2") (pin "2") (pinfunction "SWDIO/TMS_2") (pintype "passive"))
      (node (ref "MOD1") (pin "4") (pinfunction "SWDIO_4") (pintype "bidirectional"))
      (node (ref "U1") (pin "72") (pinfunction "SWDIO/PA13_72") (pintype "bidirectional"))
    )
    (net (code "86") (name "TGT_SWO") (class "Default")
      (node (ref "CON2") (pin "6") (pinfunction "SWO/TDO_6") (pintype "passive"))
      (node (ref "U1") (pin "89") (pinfunction "SWO/PB3_89") (pintype "bidirectional"))
    )
    (net (code "87") (name "TGT_TX") (class "Default")
      (node (ref "MOD1") (pin "7") (pinfunction "TGT_TX_7") (pintype "bidirectional"))
      (node (ref "U1") (pin "68") (pinfunction "TGT_TX/PA9_68") (pintype "bidirectional"))
    )
    (net (code "88") (name "unconnected-(IC4-NC1-Pad1)") (class "Default")
      (node (ref "IC4") (pin "1") (pinfunction "NC1_1") (pintype "bidirectional"))
    )
    (net (code "89") (name "unconnected-(IC4-NC2-Pad2)") (class "Default")
      (node (ref "IC4") (pin "2") (pinfunction "NC2_2") (pintype "bidirectional"))
    )
    (net (code "90") (name "unconnected-(IC4-NC3-Pad3)") (class "Default")
      (node (ref "IC4") (pin "3") (pinfunction "NC3_3") (pintype "bidirectional"))
    )
    (net (code "91") (name "unconnected-(IC4-NC7-Pad7)") (class "Default")
      (node (ref "IC4") (pin "7") (pinfunction "NC7_7") (pintype "bidirectional"))
    )
    (net (code "92") (name "unconnected-(MOD1-5V-USB-Pad3)") (class "Default")
      (node (ref "MOD1") (pin "3") (pinfunction "5V-USB_3") (pintype "bidirectional"))
    )
  )
)
